# Tiny817_Xplained_Pro_current_measurement.net
KiCad netlist of a schematic drawn in Altium Designer
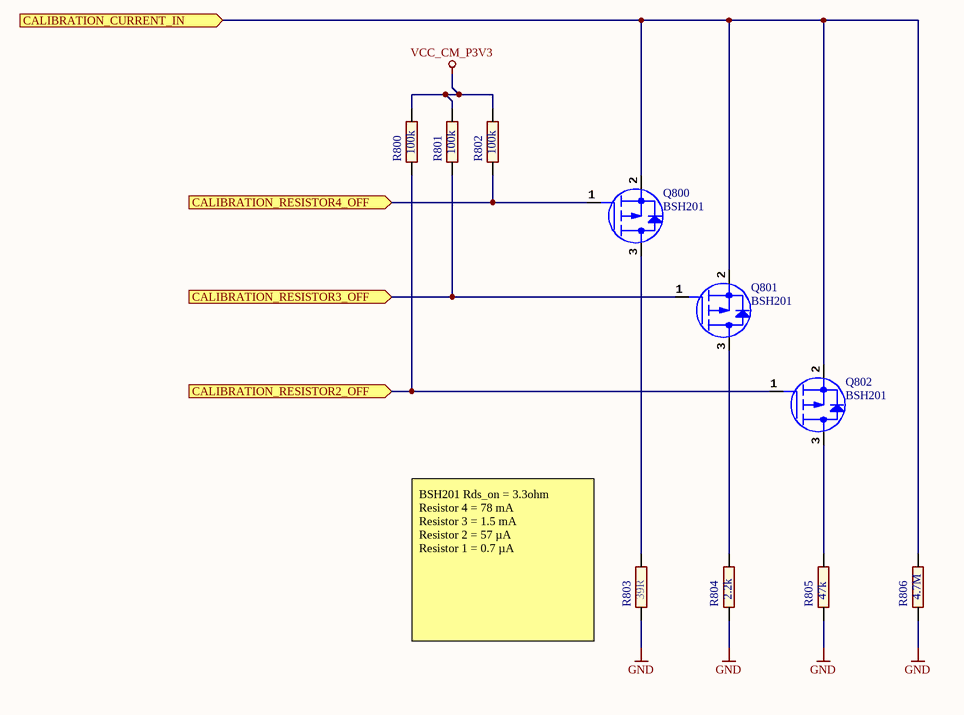
[diagram p0: Tiny817_Xplained_Pro_current_measurement_calibration.SchDoc]

(export (version "E")
  (design (tool "Eeschema 10.0.6"))
  (components
    (comp (ref "Q800")
      (value "BSH201")
      (footprint "AP5-00002")
      (fields (field (name "MANUFACTURER") "NXP") (field (name "MPN") "BSH201,215"))
      (libsource (lib "AltiumDbLib") (part "MOSFET_P_GSD"))
    )
    (comp (ref "Q801")
      (value "BSH201")
      (footprint "AP5-00002")
      (fields (field (name "MANUFACTURER") "NXP") (field (name "MPN") "BSH201,215"))
      (libsource (lib "AltiumDbLib") (part "MOSFET_P_GSD"))
    )
    (comp (ref "Q802")
      (value "BSH201")
      (footprint "AP5-00002")
      (fields (field (name "MANUFACTURER") "NXP") (field (name "MPN") "BSH201,215"))
      (libsource (lib "AltiumDbLib") (part "MOSFET_P_GSD"))
    )
    (comp (ref "R800")
      (value "100k")
      (footprint "AP2-00011")
      (description "Thick film resistor, SMD 0402, 1/16W, 1%")
      (fields (field (name "TOLERANCE") "1 %") (field (name "MANUFACTURER") "ASJ"))
      (libsource (lib "AltiumDbLib") (part "R2"))
    )
    (comp (ref "R801")
      (value "100k")
      (footprint "AP2-00011")
      (description "Thick film resistor, SMD 0402, 1/16W, 1%")
      (fields (field (name "TOLERANCE") "1 %") (field (name "MANUFACTURER") "ASJ"))
      (libsource (lib "AltiumDbLib") (part "R2"))
    )
    (comp (ref "R802")
      (value "100k")
      (footprint "AP2-00011")
      (description "Thick film resistor, SMD 0402, 1/16W, 1%")
      (fields (field (name "TOLERANCE") "1 %") (field (name "MANUFACTURER") "ASJ"))
      (libsource (lib "AltiumDbLib") (part "R2"))
    )
    (comp (ref "R803")
      (value "39R")
      (footprint "AP2-00011")
      (description "Thick film resistor, SMD 0402, 1/16W, 1%")
      (fields (field (name "TOLERANCE") "1 %") (field (name "MANUFACTURER") "ASJ"))
      (libsource (lib "AltiumDbLib") (part "R2"))
    )
    (comp (ref "R804")
      (value "2.2k")
      (footprint "AP2-00011")
      (description "Thick film resistor, SMD 0402, 1/16W, 1%")
      (fields (field (name "TOLERANCE") "1 %") (field (name "MANUFACTURER") "ASJ"))
      (libsource (lib "AltiumDbLib") (part "R2"))
    )
    (comp (ref "R805")
      (value "47k")
      (footprint "AP2-00011")
      (description "Thick film resistor, SMD 0402, 1/16W, 1%")
      (fields (field (name "TOLERANCE") "1 %") (field (name "MANUFACTURER") "KOA"))
      (libsource (lib "AltiumDbLib") (part "R2"))
    )
    (comp (ref "R806")
      (value "4.7M")
      (footprint "AP2-00011")
      (description "Thick film SMD 0402 1/16W 1%")
      (fields (field (name "TOLERANCE") "1 %") (field (name "MANUFACTURER") "YAGEO CORP"))
      (libsource (lib "AltiumDbLib") (part "R2"))
    )
  )
  (nets
    (net (code "1") (name "/CALIBRATION_CURRENT_IN") (class "Default")
      (node (ref "Q800") (pin "2") (pinfunction "S_2") (pintype "passive"))
      (node (ref "Q801") (pin "2") (pinfunction "S_2") (pintype "passive"))
      (node (ref "Q802") (pin "2") (pinfunction "S_2") (pintype "passive"))
      (node (ref "R806") (pin "2") (pinfunction "2_2") (pintype "passive"))
    )
    (net (code "2") (name "/CALIBRATION_RESISTOR2_OFF") (class "Default")
      (node (ref "Q802") (pin "1") (pinfunction "G_1") (pintype "passive"))
      (node (ref "R800") (pin "1") (pinfunction "1_1") (pintype "passive"))
    )
    (net (code "3") (name "/CALIBRATION_RESISTOR3_OFF") (class "Default")
      (node (ref "Q801") (pin "1") (pinfunction "G_1") (pintype "passive"))
      (node (ref "R801") (pin "1") (pinfunction "1_1") (pintype "passive"))
    )
    (net (code "4") (name "/CALIBRATION_RESISTOR4_OFF") (class "Default")
      (node (ref "Q800") (pin "1") (pinfunction "G_1") (pintype "passive"))
      (node (ref "R802") (pin "1") (pinfunction "1_1") (pintype "passive"))
    )
    (net (code "5") (name "GND") (class "Default")
      (node (ref "R803") (pin "1") (pinfunction "1_1") (pintype "passive"))
      (node (ref "R804") (pin "1") (pinfunction "1_1") (pintype "passive"))
      (node (ref "R805") (pin "1") (pinfunction "1_1") (pintype "passive"))
      (node (ref "R806") (pin "1") (pinfunction "1_1") (pintype "passive"))
    )
    (net (code "6") (name "Net-(Q800-D)") (class "Default")
      (node (ref "Q800") (pin "3") (pinfunction "D_3") (pintype "passive"))
      (node (ref "R803") (pin "2") (pinfunction "2_2") (pintype "passive"))
    )
    (net (code "7") (name "Net-(Q801-D)") (class "Default")
      (node (ref "Q801") (pin "3") (pinfunction "D_3") (pintype "passive"))
      (node (ref "R804") (pin "2") (pinfunction "2_2") (pintype "passive"))
    )
    (net (code "8") (name "Net-(Q802-D)") (class "Default")
      (node (ref "Q802") (pin "3") (pinfunction "D_3") (pintype "passive"))
      (node (ref "R805") (pin "2") (pinfunction "2_2") (pintype "passive"))
    )
    (net (code "9") (name "VCC_CM_P3V3") (class "Default")
      (node (ref "R800") (pin "2") (pinfunction "2_2") (pintype "passive"))
      (node (ref "R801") (pin "2") (pinfunction "2_2") (pintype "passive"))
      (node (ref "R802") (pin "2") (pinfunction "2_2") (pintype "passive"))
    )
  )
)
